# Sensors.net
KiCad netlist of a schematic drawn in Altium Designer
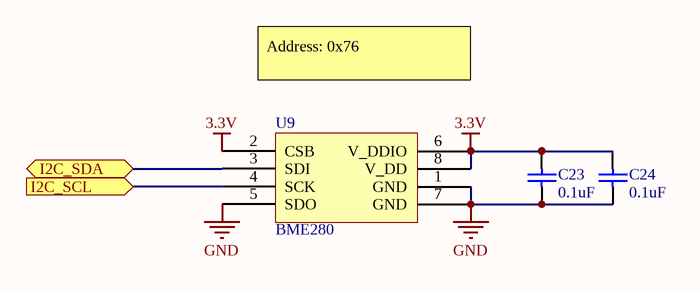
[diagram p0: Sensors.SchDoc]

(export (version "E")
  (design (tool "Eeschema 10.0.6"))
  (components
    (comp (ref "C23")
      (value "0.1uF")
      (footprint "0603_CAP")
      (fields (field (name "Comment") "Capacitor"))
      (libsource (lib "Passive_comp") (part "Capacitor"))
    )
    (comp (ref "C24")
      (value "0.1uF")
      (footprint "0603_CAP")
      (fields (field (name "Comment") "Capacitor"))
      (libsource (lib "Passive_comp") (part "Capacitor"))
    )
    (comp (ref "U9")
      (value "BME280")
      (footprint "BME280")
      (description "Combined humidity and pressure sensor")
      (libsource (lib "Sensors") (part "BME280"))
    )
  )
  (nets
    (net (code "1") (name "/I2C_SCL") (class "Default")
      (node (ref "U9") (pin "4") (pinfunction "SCK_4") (pintype "passive"))
    )
    (net (code "2") (name "/I2C_SDA") (class "Default")
      (node (ref "U9") (pin "3") (pinfunction "SDI_3") (pintype "passive"))
    )
    (net (code "3") (name "3.3V") (class "Default")
      (node (ref "C23") (pin "2") (pinfunction "2_2") (pintype "passive"))
      (node (ref "C24") (pin "2") (pinfunction "2_2") (pintype "passive"))
      (node (ref "U9") (pin "2") (pinfunction "CSB_2") (pintype "passive"))
      (node (ref "U9") (pin "6") (pinfunction "V_DDIO_6") (pintype "passive"))
      (node (ref "U9") (pin "8") (pinfunction "V_DD_8") (pintype "passive"))
    )
    (net (code "4") (name "GND") (class "Default")
      (node (ref "C23") (pin "1") (pinfunction "1_1") (pintype "passive"))
      (node (ref "C24") (pin "1") (pinfunction "1_1") (pintype "passive"))
      (node (ref "U9") (pin "1") (pinfunction "GND_1") (pintype "passive"))
      (node (ref "U9") (pin "5") (pinfunction "SDO_5") (pintype "passive"))
      (node (ref "U9") (pin "7") (pinfunction "GND_7") (pintype "passive"))
    )
  )
)
